# Haar_HardMount.net
KiCad netlist of a schematic drawn in EAGLE
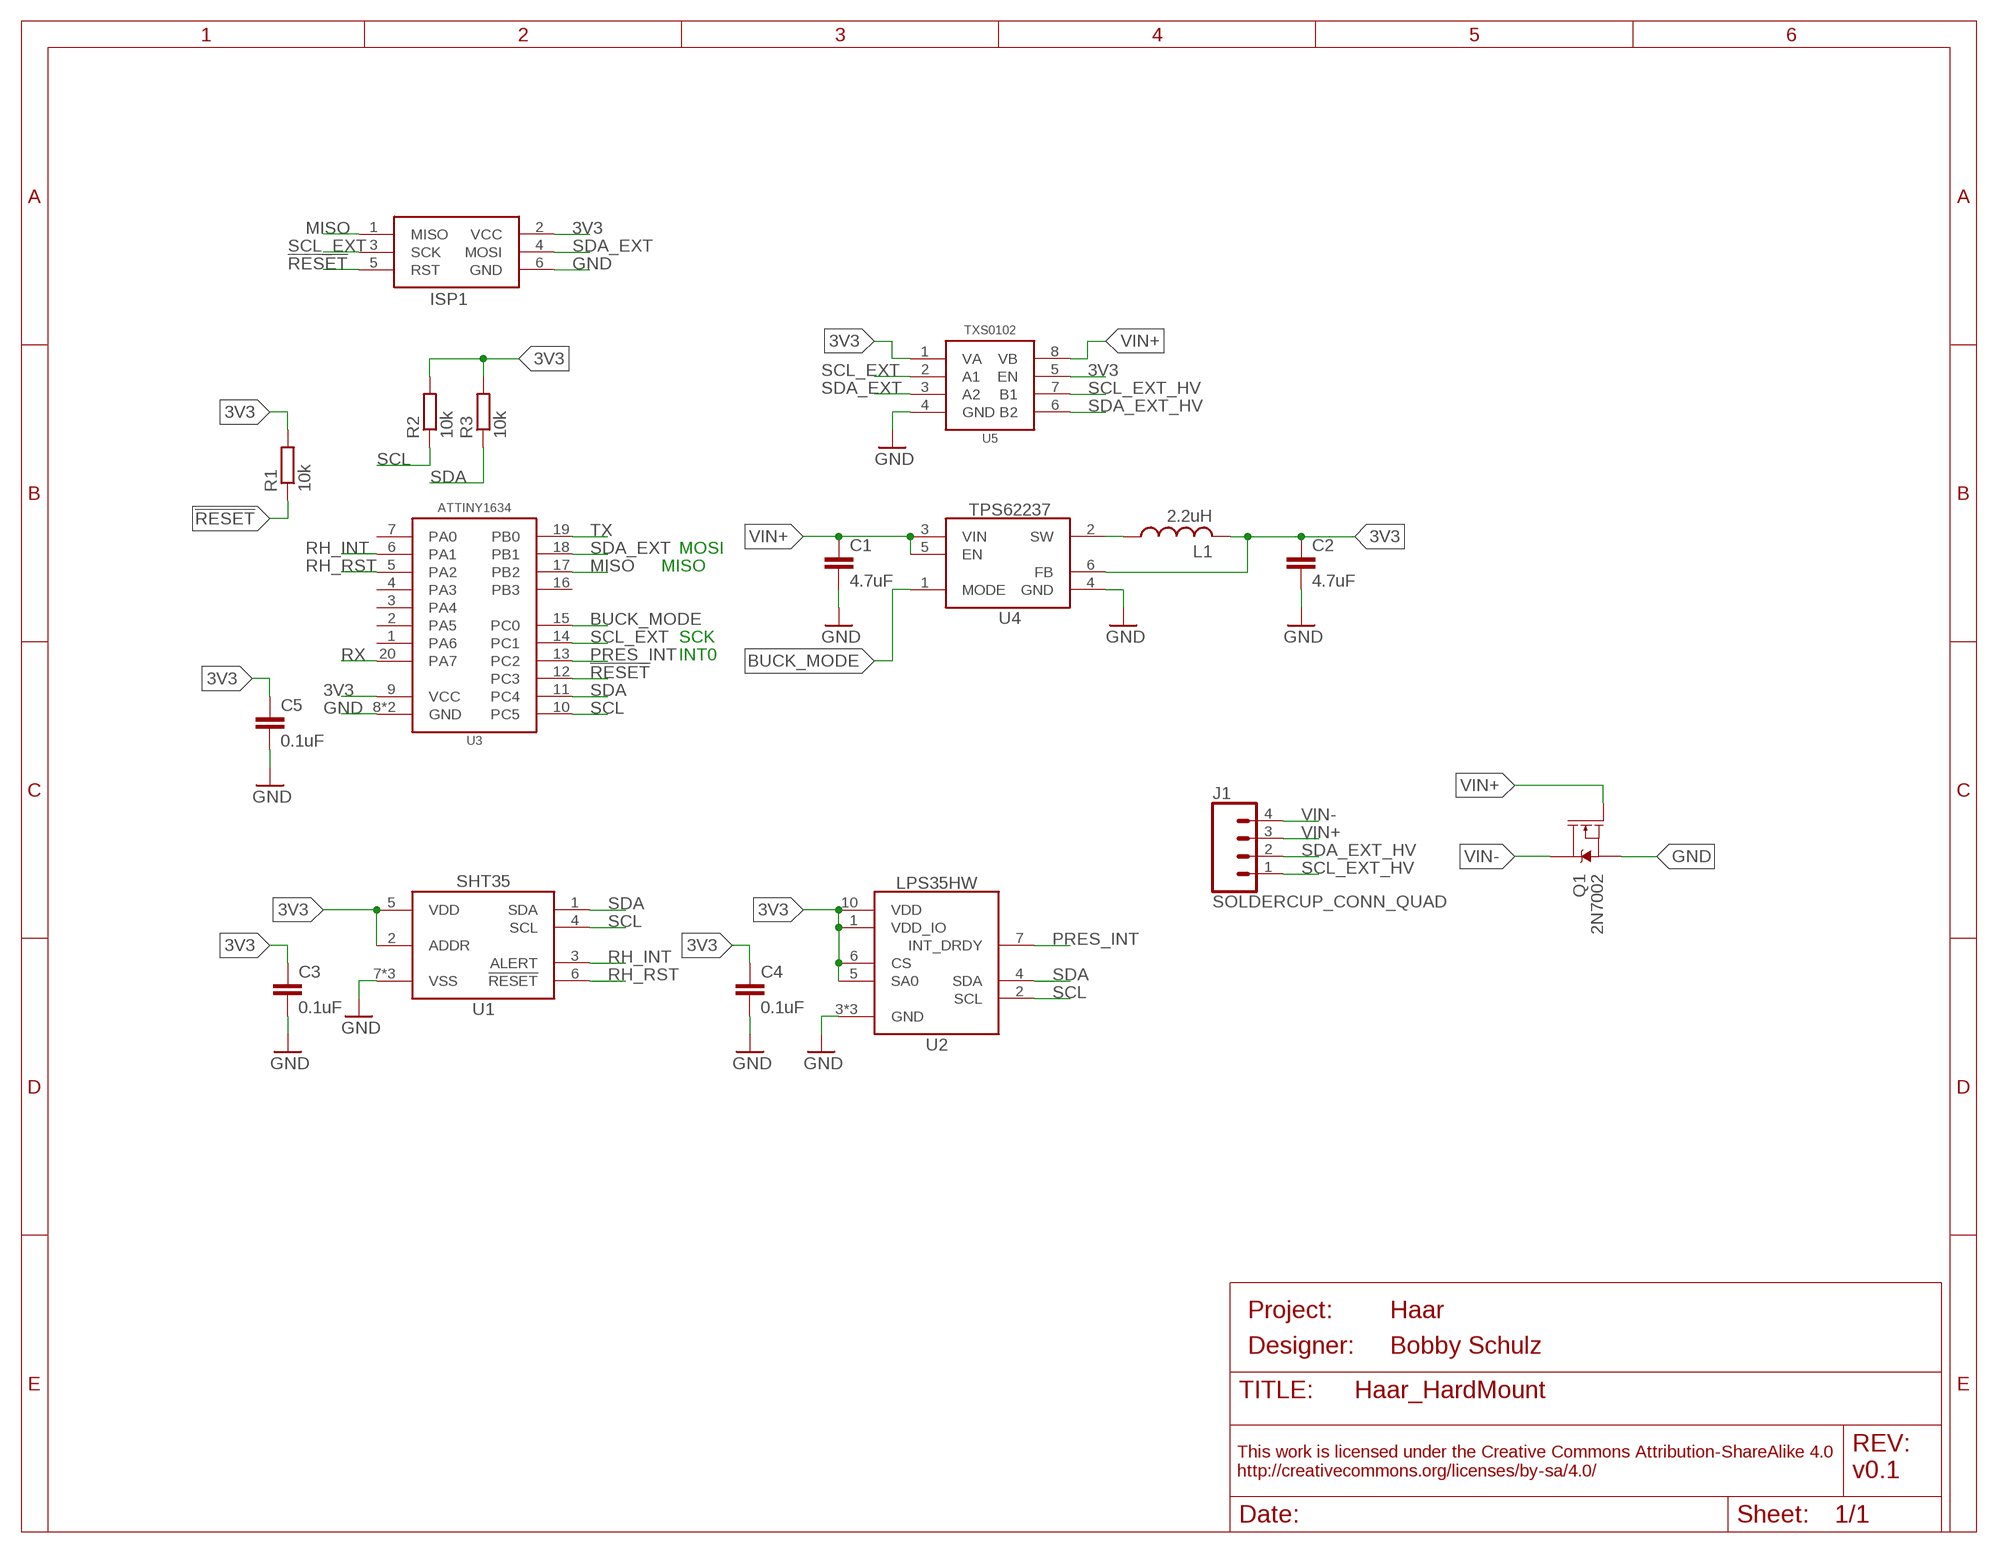
[diagram p0: schematic, sheet 1]

(export (version "E")
  (design (tool "Eeschema 10.0.6"))
  (components
    (comp (ref "C1")
      (value "4.7uF")
      (footprint "eagle-import:C0402")
      (fields
        (field (name "DIGIKEY") "490-14306-1-ND")
        (field (name "MF") "Murata")
        (field (name "MPN") "GRM155R61A475MEAAD")
      )
      (libsource (lib "eagle-import") (part "C-EUC0402"))
    )
    (comp (ref "C2")
      (value "4.7uF")
      (footprint "eagle-import:C0402")
      (fields
        (field (name "DIGIKEY") "490-14306-1-ND")
        (field (name "MF") "Murata")
        (field (name "MPN") "GRM155R61A475MEAAD")
      )
      (libsource (lib "eagle-import") (part "C-EUC0402"))
    )
    (comp (ref "C3")
      (value "0.1uF")
      (footprint "eagle-import:C0402")
      (fields (field (name "MF") "Murata") (field (name "MPN") "GCM155R71C104KA55D"))
      (libsource (lib "eagle-import") (part "C-EUC04020.1UF"))
    )
    (comp (ref "C4")
      (value "0.1uF")
      (footprint "eagle-import:C0402")
      (fields (field (name "MF") "Murata") (field (name "MPN") "GCM155R71C104KA55D"))
      (libsource (lib "eagle-import") (part "C-EUC04020.1UF"))
    )
    (comp (ref "C5")
      (value "0.1uF")
      (footprint "eagle-import:C0402")
      (fields (field (name "MF") "Murata") (field (name "MPN") "GCM155R71C104KA55D"))
      (libsource (lib "eagle-import") (part "C-EUC04020.1UF"))
    )
    (comp (ref "ISP1")
      (value "AVRISP1.27MM")
      (footprint "eagle-import:2X3_1.27")
      (libsource (lib "eagle-import") (part "AVRISP1.27MM"))
    )
    (comp (ref "J1")
      (value "SOLDERCUP_CONN_QUAD")
      (footprint "eagle-import:SOLDERCUP_CONN_QUAD")
      (libsource (lib "eagle-import") (part "SOLDERCUP_CONN_QUAD"))
    )
    (comp (ref "L1")
      (value "2.2uH")
      (footprint "eagle-import:0805")
      (fields (field (name "MF") "Wurth") (field (name "MPN") "74479775222"))
      (libsource (lib "eagle-import") (part "INDUCTOR0805"))
    )
    (comp (ref "Q1")
      (value "2N7002")
      (footprint "eagle-import:SOT323")
      (fields (field (name "MF") "Diodes Incorporated") (field (name "MPN") "2N7002W-7-F"))
      (libsource (lib "eagle-import") (part "MOSFET-NCH-2N7002PW"))
    )
    (comp (ref "R1")
      (value "10k")
      (footprint "eagle-import:R0402")
      (fields (field (name "MF") "Yageo") (field (name "MPN") "RC0603FR-0710KL"))
      (libsource (lib "eagle-import") (part "R-EU_R040210K"))
    )
    (comp (ref "R2")
      (value "10k")
      (footprint "eagle-import:R0402")
      (fields (field (name "MF") "Yageo") (field (name "MPN") "RC0603FR-0710KL"))
      (libsource (lib "eagle-import") (part "R-EU_R040210K"))
    )
    (comp (ref "R3")
      (value "10k")
      (footprint "eagle-import:R0402")
      (fields (field (name "MF") "Yageo") (field (name "MPN") "RC0603FR-0710KL"))
      (libsource (lib "eagle-import") (part "R-EU_R040210K"))
    )
    (comp (ref "U1")
      (value "SHT35DFN")
      (footprint "eagle-import:DFN_8_2.5X2.5")
      (fields
        (field (name "DISP") "SHT35")
        (field (name "MF") "Sensirion")
        (field (name "MPN") "SHT35-DIS-F2.5KS")
      )
      (libsource (lib "eagle-import") (part "SHT3DFN5"))
    )
    (comp (ref "U2")
      (value "LPS35HW")
      (footprint "eagle-import:CCLGA10L")
      (fields (field (name "DISP") "LPS35HW") (field (name "MF") "ST") (field (name "MPN") "LPS35HWTR"))
      (libsource (lib "eagle-import") (part "LPS3HW5"))
    )
    (comp (ref "U3")
      (value "ATTINY1634QFN")
      (footprint "eagle-import:QFN20")
      (fields (field (name "MF") "Atmel") (field (name "MPN") "ATTINY1634-MUR"))
      (libsource (lib "eagle-import") (part "ATTINY1634QFN"))
    )
    (comp (ref "U4")
      (value "TPS62237DRY")
      (footprint "eagle-import:DRY0006A")
      (fields (field (name "DISP") "TPS62237") (field (name "MF") "TI") (field (name "MPN") "TPS62237DRYR"))
      (libsource (lib "eagle-import") (part "TPS6223DRY7"))
    )
    (comp (ref "U5")
      (value "TXS0102DQM")
      (footprint "eagle-import:DQM_R-PX2SON-N8")
      (fields (field (name "MF") "TI") (field (name "MPN") "TXS0102DQMR"))
      (libsource (lib "eagle-import") (part "TXS0102DQM"))
    )
  )
  (nets
    (net (code "1") (name "/MISO") (class "Default")
      (node (ref "ISP1") (pin "1") (pinfunction "MISO_1") (pintype "input"))
      (node (ref "U3") (pin "17") (pinfunction "PB2_17") (pintype "bidirectional"))
    )
    (net (code "2") (name "/PRES_INT") (class "Default")
      (node (ref "U2") (pin "7") (pinfunction "INT_DRDY_7") (pintype "output"))
      (node (ref "U3") (pin "13") (pinfunction "PC2_13") (pintype "bidirectional"))
    )
    (net (code "3") (name "/RH_INT") (class "Default")
      (node (ref "U1") (pin "3") (pinfunction "ALERT_3") (pintype "output"))
      (node (ref "U3") (pin "6") (pinfunction "PA1_6") (pintype "bidirectional"))
    )
    (net (code "4") (name "/RH_RST") (class "Default")
      (node (ref "U1") (pin "6") (pinfunction "~{RESET}_6") (pintype "input"))
      (node (ref "U3") (pin "5") (pinfunction "PA2_5") (pintype "bidirectional"))
    )
    (net (code "5") (name "/RX") (class "Default")
      (node (ref "U3") (pin "20") (pinfunction "PA7_20") (pintype "bidirectional"))
    )
    (net (code "6") (name "/SCL") (class "Default")
      (node (ref "R2") (pin "1") (pinfunction "1_1") (pintype "passive"))
      (node (ref "U1") (pin "4") (pinfunction "SCL_4") (pintype "input"))
      (node (ref "U2") (pin "2") (pinfunction "SCL_2") (pintype "input"))
      (node (ref "U3") (pin "10") (pinfunction "PC5_10") (pintype "bidirectional"))
    )
    (net (code "7") (name "/SCL_EXT") (class "Default")
      (node (ref "ISP1") (pin "3") (pinfunction "SCK_3") (pintype "output"))
      (node (ref "U3") (pin "14") (pinfunction "PC1_14") (pintype "bidirectional"))
      (node (ref "U5") (pin "2") (pinfunction "A1_2") (pintype "bidirectional"))
    )
    (net (code "8") (name "/SCL_EXT_HV") (class "Default")
      (node (ref "J1") (pin "1") (pinfunction "1_1") (pintype "passive"))
      (node (ref "U5") (pin "7") (pinfunction "B1_7") (pintype "bidirectional"))
    )
    (net (code "9") (name "/SDA") (class "Default")
      (node (ref "R3") (pin "1") (pinfunction "1_1") (pintype "passive"))
      (node (ref "U1") (pin "1") (pinfunction "SDA_1") (pintype "bidirectional"))
      (node (ref "U2") (pin "4") (pinfunction "SDA_4") (pintype "bidirectional"))
      (node (ref "U3") (pin "11") (pinfunction "PC4_11") (pintype "bidirectional"))
    )
    (net (code "10") (name "/SDA_EXT") (class "Default")
      (node (ref "ISP1") (pin "4") (pinfunction "MOSI_4") (pintype "output"))
      (node (ref "U3") (pin "18") (pinfunction "PB1_18") (pintype "bidirectional"))
      (node (ref "U5") (pin "3") (pinfunction "A2_3") (pintype "bidirectional"))
    )
    (net (code "11") (name "/SDA_EXT_HV") (class "Default")
      (node (ref "J1") (pin "2") (pinfunction "2_2") (pintype "passive"))
      (node (ref "U5") (pin "6") (pinfunction "B2_6") (pintype "bidirectional"))
    )
    (net (code "12") (name "/TX") (class "Default")
      (node (ref "U3") (pin "19") (pinfunction "PB0_19") (pintype "bidirectional"))
    )
    (net (code "13") (name "/~{RESET}") (class "Default")
      (node (ref "ISP1") (pin "5") (pinfunction "RST_5") (pintype "output"))
      (node (ref "R1") (pin "1") (pinfunction "1_1") (pintype "passive"))
      (node (ref "U3") (pin "12") (pinfunction "PC3_12") (pintype "bidirectional"))
    )
    (net (code "14") (name "3V3") (class "Default")
      (node (ref "C2") (pin "1") (pinfunction "1_1") (pintype "passive"))
      (node (ref "C3") (pin "1") (pinfunction "1_1") (pintype "passive"))
      (node (ref "C4") (pin "1") (pinfunction "1_1") (pintype "passive"))
      (node (ref "C5") (pin "1") (pinfunction "1_1") (pintype "passive"))
      (node (ref "ISP1") (pin "2") (pinfunction "VCC_2") (pintype "power_in"))
      (node (ref "L1") (pin "2") (pinfunction "2_2") (pintype "passive"))
      (node (ref "R1") (pin "2") (pinfunction "2_2") (pintype "passive"))
      (node (ref "R2") (pin "2") (pinfunction "2_2") (pintype "passive"))
      (node (ref "R3") (pin "2") (pinfunction "2_2") (pintype "passive"))
      (node (ref "U1") (pin "2") (pinfunction "ADDR_2") (pintype "input"))
      (node (ref "U1") (pin "5") (pinfunction "VDD_5") (pintype "power_in"))
      (node (ref "U2") (pin "1") (pinfunction "VDD_IO_1") (pintype "power_in"))
      (node (ref "U2") (pin "10") (pinfunction "VDD_10") (pintype "power_in"))
      (node (ref "U2") (pin "5") (pinfunction "SA0_5") (pintype "input"))
      (node (ref "U2") (pin "6") (pinfunction "CS_6") (pintype "input"))
      (node (ref "U3") (pin "9") (pinfunction "VCC_9") (pintype "power_in"))
      (node (ref "U4") (pin "6") (pinfunction "FB_6") (pintype "input"))
      (node (ref "U5") (pin "1") (pinfunction "VA_1") (pintype "power_in"))
      (node (ref "U5") (pin "5") (pinfunction "EN_5") (pintype "input"))
    )
    (net (code "15") (name "BUCK_MODE") (class "Default")
      (node (ref "U3") (pin "15") (pinfunction "PC0_15") (pintype "bidirectional"))
      (node (ref "U4") (pin "1") (pinfunction "MODE_1") (pintype "input"))
    )
    (net (code "16") (name "GND") (class "Default")
      (node (ref "C1") (pin "2") (pinfunction "2_2") (pintype "passive"))
      (node (ref "C2") (pin "2") (pinfunction "2_2") (pintype "passive"))
      (node (ref "C3") (pin "2") (pinfunction "2_2") (pintype "passive"))
      (node (ref "C4") (pin "2") (pinfunction "2_2") (pintype "passive"))
      (node (ref "C5") (pin "2") (pinfunction "2_2") (pintype "passive"))
      (node (ref "ISP1") (pin "6") (pinfunction "GND_6") (pintype "power_in"))
      (node (ref "Q1") (pin "2") (pinfunction "S_2") (pintype "bidirectional"))
      (node (ref "U1") (pin "7") (pinfunction "VSS_7") (pintype "power_in"))
      (node (ref "U1") (pin "8") (pinfunction "VSS_8") (pintype "power_in"))
      (node (ref "U1") (pin "EP") (pinfunction "VSS_EP") (pintype "power_in"))
      (node (ref "U2") (pin "3") (pinfunction "GND_3") (pintype "power_in"))
      (node (ref "U2") (pin "8") (pinfunction "GND_8") (pintype "power_in"))
      (node (ref "U2") (pin "9") (pinfunction "GND_9") (pintype "power_in"))
      (node (ref "U3") (pin "8") (pinfunction "GND_8") (pintype "power_in"))
      (node (ref "U3") (pin "EP") (pinfunction "GND_EP") (pintype "power_in"))
      (node (ref "U4") (pin "4") (pinfunction "GND_4") (pintype "power_in"))
      (node (ref "U5") (pin "4") (pinfunction "GND_4") (pintype "power_in"))
    )
    (net (code "17") (name "Net-(U4-SW)") (class "Default")
      (node (ref "L1") (pin "1") (pinfunction "1_1") (pintype "passive"))
      (node (ref "U4") (pin "2") (pinfunction "SW_2") (pintype "output"))
    )
    (net (code "18") (name "VIN+") (class "Default")
      (node (ref "C1") (pin "1") (pinfunction "1_1") (pintype "passive"))
      (node (ref "J1") (pin "3") (pinfunction "3_3") (pintype "passive"))
      (node (ref "Q1") (pin "1") (pinfunction "G_1") (pintype "bidirectional"))
      (node (ref "U4") (pin "3") (pinfunction "VIN_3") (pintype "power_in"))
      (node (ref "U4") (pin "5") (pinfunction "EN_5") (pintype "input"))
      (node (ref "U5") (pin "8") (pinfunction "VB_8") (pintype "power_in"))
    )
    (net (code "19") (name "VIN-") (class "Default")
      (node (ref "J1") (pin "4") (pinfunction "4_4") (pintype "passive"))
      (node (ref "Q1") (pin "3") (pinfunction "D_3") (pintype "bidirectional"))
    )
    (net (code "20") (name "unconnected-(U3-PA0-Pad7)") (class "Default")
      (node (ref "U3") (pin "7") (pinfunction "PA0_7") (pintype "bidirectional"))
    )
    (net (code "21") (name "unconnected-(U3-PA3-Pad4)") (class "Default")
      (node (ref "U3") (pin "4") (pinfunction "PA3_4") (pintype "bidirectional"))
    )
    (net (code "22") (name "unconnected-(U3-PA4-Pad3)") (class "Default")
      (node (ref "U3") (pin "3") (pinfunction "PA4_3") (pintype "bidirectional"))
    )
    (net (code "23") (name "unconnected-(U3-PA5-Pad2)") (class "Default")
      (node (ref "U3") (pin "2") (pinfunction "PA5_2") (pintype "bidirectional"))
    )
    (net (code "24") (name "unconnected-(U3-PA6-Pad1)") (class "Default")
      (node (ref "U3") (pin "1") (pinfunction "PA6_1") (pintype "bidirectional"))
    )
    (net (code "25") (name "unconnected-(U3-PB3-Pad16)") (class "Default")
      (node (ref "U3") (pin "16") (pinfunction "PB3_16") (pintype "bidirectional"))
    )
  )
)
